# Schematic_Rev2.net
KiCad netlist of a schematic drawn in Altium Designer
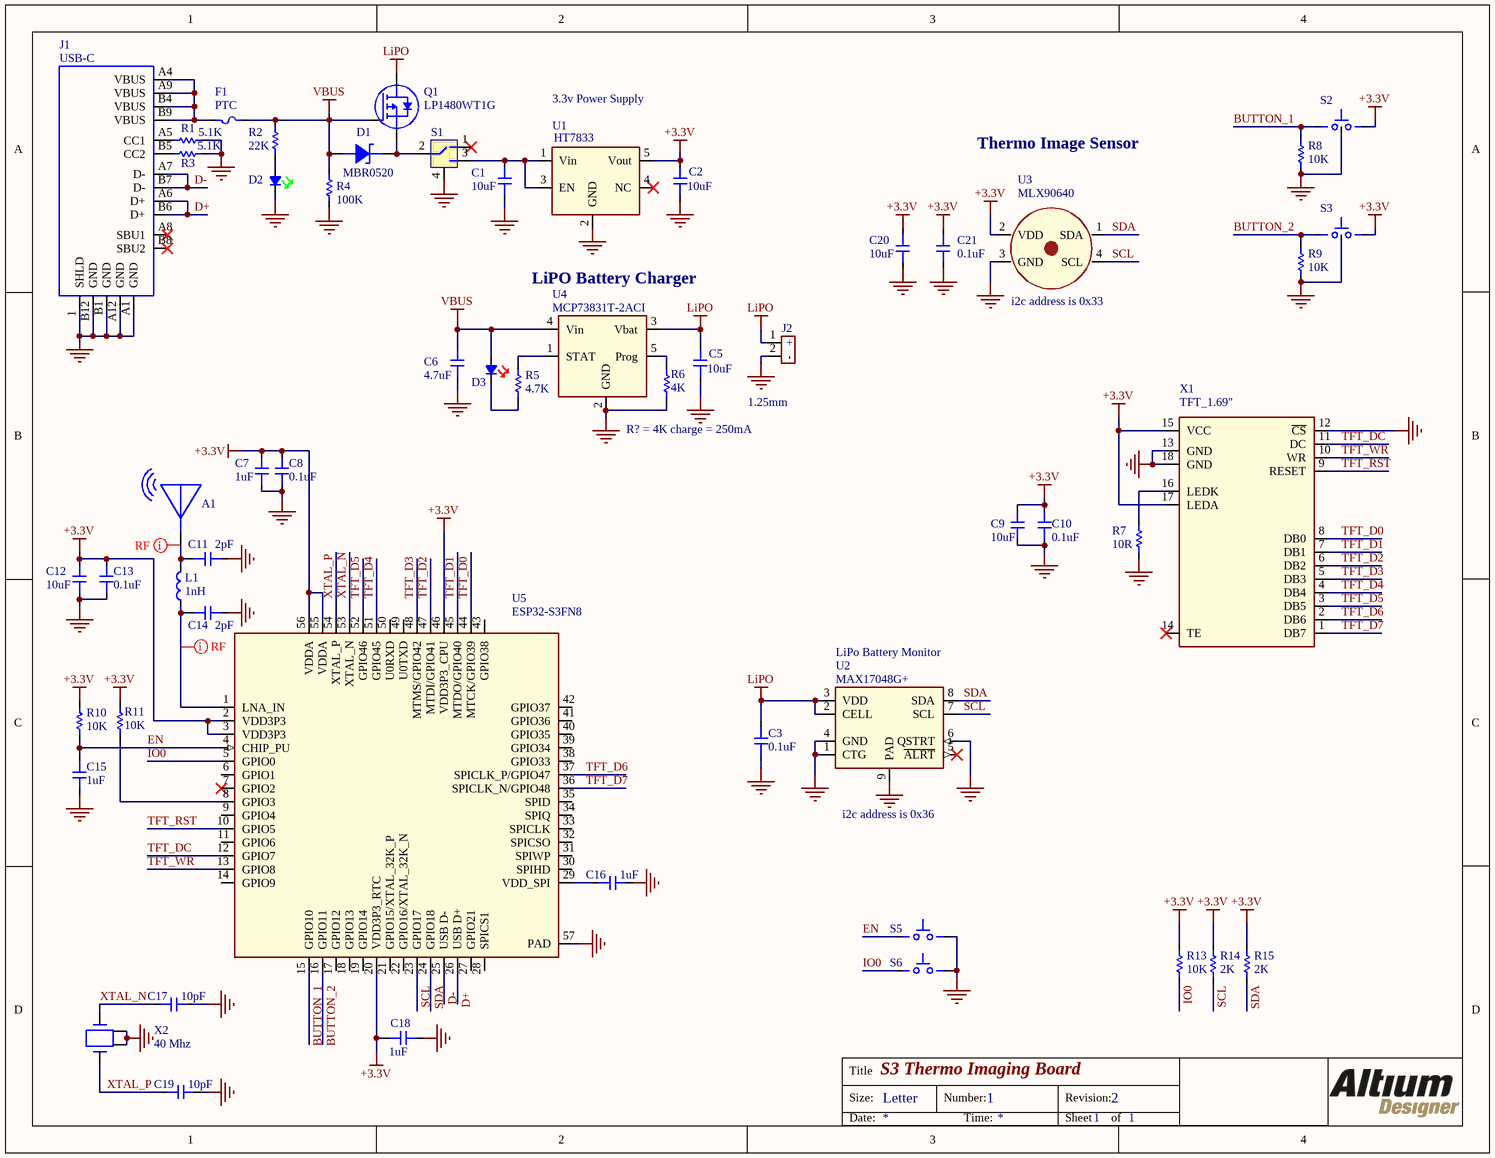
[diagram p0: Schematic_Rev2.SchDoc]

(export (version "E")
  (design (tool "Eeschema 10.0.6"))
  (components
    (comp (ref "A1")
      (value "ANT3216LL00R2400A")
      (footprint "ANT3216LL00R2400A")
      (description "Antenna Chip 2.4Gig")
      (fields (field (name "MANUFACTURER") "YAGEO"))
      (libsource (lib "MAR") (part "ANT3216LL00R2400A"))
    )
    (comp (ref "C1")
      (value "10uF")
      (footprint "CAPC2012X140N")
      (description "CAP 10uF 50V 0805")
      (libsource (lib "MAR") (part "CAP_0805"))
    )
    (comp (ref "C2")
      (value "10uF")
      (footprint "CAPC2012X140N")
      (description "CAP 10uF 50V 0805")
      (libsource (lib "MAR") (part "CAP_0805"))
    )
    (comp (ref "C3")
      (value "0.1uF")
      (footprint "CAPC1005X56N")
      (description "CAP 0.1uF 0402")
      (libsource (lib "MAR") (part "CAP_0402"))
    )
    (comp (ref "C5")
      (value "10uF")
      (footprint "CAPC2012X140N")
      (description "CAP 10uF 50V 0805")
      (libsource (lib "MAR") (part "CAP_0805"))
    )
    (comp (ref "C6")
      (value "4.7uF")
      (footprint "CAPC2012X140N")
      (description "CAP 4.7uF 0805")
      (libsource (lib "MAR") (part "CAP_0805"))
    )
    (comp (ref "C7")
      (value "1uF")
      (footprint "CAPC1608X09L")
      (description "CAP 1uF 0603")
      (libsource (lib "MAR") (part "CAP_0603"))
    )
    (comp (ref "C8")
      (value "0.1uF")
      (footprint "CAPC1608X09L")
      (description "CAP 0.1uF 0603")
      (libsource (lib "MAR") (part "CAP_0603"))
    )
    (comp (ref "C9")
      (value "10uF")
      (footprint "CAPC2012X140N")
      (description "CAP 10uF 0805")
      (libsource (lib "MAR") (part "CAP_0805"))
    )
    (comp (ref "C10")
      (value "0.1uF")
      (footprint "CAPC1608X09L")
      (description "CAP 0.1uF 0603")
      (libsource (lib "MAR") (part "CAP_0603"))
    )
    (comp (ref "C11")
      (value "2pF")
      (footprint "CAPC1005X56N")
      (description "CAP 2pF 0402")
      (libsource (lib "MAR") (part "CAP_0402"))
    )
    (comp (ref "C12")
      (value "10uF")
      (footprint "CAPC2012X140N")
      (description "CAP 10uF 50V 0805")
      (libsource (lib "MAR") (part "CAP_0805"))
    )
    (comp (ref "C13")
      (value "0.1uF")
      (footprint "CAPC1005X56N")
      (description "CAP 0.1uF 0402")
      (libsource (lib "MAR") (part "CAP_0402"))
    )
    (comp (ref "C14")
      (value "2pF")
      (footprint "CAPC1005X56N")
      (description "CAP 2pF 0402")
      (libsource (lib "MAR") (part "CAP_0402"))
    )
    (comp (ref "C15")
      (value "1uF")
      (footprint "CAPC1005X56N")
      (description "CAP 1uF 0402")
      (libsource (lib "MAR") (part "CAP_0402"))
    )
    (comp (ref "C16")
      (value "1uF")
      (footprint "CAPC1005X56N")
      (description "CAP 1uF 0402")
      (libsource (lib "MAR") (part "CAP_0402"))
    )
    (comp (ref "C17")
      (value "10pF")
      (footprint "CAPC1005X56N")
      (description "CAP 10pF 0402")
      (libsource (lib "MAR") (part "CAP_0402"))
    )
    (comp (ref "C18")
      (value "1uF")
      (footprint "CAPC1608X09L")
      (description "CAP 1uF 0603")
      (libsource (lib "MAR") (part "CAP_0603"))
    )
    (comp (ref "C19")
      (value "10pF")
      (footprint "CAPC1005X56N")
      (description "CAP 10pF 0402")
      (libsource (lib "MAR") (part "CAP_0402"))
    )
    (comp (ref "C20")
      (value "10uF")
      (footprint "CAPC2012X140N")
      (description "CAP 10uF 50V 0805")
      (libsource (lib "MAR") (part "CAP_0805"))
    )
    (comp (ref "C21")
      (value "0.1uF")
      (footprint "CAPC1608X09L")
      (description "CAP 0.1uF 0603")
      (libsource (lib "MAR") (part "CAP_0603"))
    )
    (comp (ref "D1")
      (value "MBR0520")
      (footprint "SOD123")
      (description "DIODE SCHOTTKY 20V 500MA SOD-123")
      (fields (field (name "MANUFACTURER") "Micro") (field (name "PART_NUMBER") "C78746"))
      (libsource (lib "MAR") (part "MBR0520-TP"))
    )
    (comp (ref "D2")
      (value "Green Led")
      (footprint "LED1005X40N-Green")
      (description "LED Green 0402")
      (fields (field (name "PART_NUMBER") "C74338"))
      (libsource (lib "MAR") (part "LED_0402_SMALL_GREEN"))
    )
    (comp (ref "D3")
      (value "Red Led")
      (footprint "LED1005X40N-Red")
      (description "LED Red 0402")
      (fields (field (name "PART_NUMBER") "C364556") (field (name "MANUFACTURER") "Lite-On"))
      (libsource (lib "MAR") (part "LED_0402_SMALL_Red"))
    )
    (comp (ref "F1")
      (value "PTC")
      (footprint "RESC1608X06L (0603 FOOTPRINT)")
      (description "PTC FUSE 0.5mA hold, 1A trip 0603")
      (fields (field (name "MANUFACTURER") "JDT Fuse") (field (name "PART_NUMBER") "C2982257"))
      (libsource (lib "MAR") (part "PTC_FUSE_0603"))
    )
    (comp (ref "J1")
      (value "USB-C")
      (footprint "TYPE-C-31-M-12")
      (description "CONN RECPT USB-C")
      (fields (field (name "MANUFACTURER") "KHE") (field (name "PART_NUMBER") "C165948"))
      (libsource (lib "MAR") (part "USB-C"))
    )
    (comp (ref "J2")
      (value "1.5mm")
      (footprint "0530470260")
      (description "MIcro Conn 2POS 1.25mm Pitch Vertical")
      (fields (field (name "PART_NUMBER") "0530470260") (field (name "MANUFACTURER") "Molex"))
      (libsource (lib "MAR") (part "Molex_onn_2Pin_1.25mm_Vert"))
    )
    (comp (ref "L1")
      (value "1nH")
      (footprint "INDC1005X40L")
      (description "Inductor 1nH 0402")
      (libsource (lib "MAR") (part "Inductor"))
    )
    (comp (ref "Q1")
      (value "LP1480WT1G")
      (footprint "SC-70")
      (description "MOSFET P-CH 20V 1.4A SC-70")
      (fields (field (name "MANUFACTURER") "LRC") (field (name "PART_NUMBER") "C172434"))
      (libsource (lib "MAR") (part "LP1480WT1G"))
    )
    (comp (ref "R1")
      (value "5.1K")
      (footprint "RESC1005X40L (0402 FOOTPRINT)")
      (description "RES 5.1K 0402")
      (libsource (lib "MAR") (part "RES_0402"))
    )
    (comp (ref "R2")
      (value "22K")
      (footprint "RESC1005X40L (0402 FOOTPRINT)")
      (description "RES 22K 0402")
      (libsource (lib "MAR") (part "RES_0402"))
    )
    (comp (ref "R3")
      (value "5.1K")
      (footprint "RESC1005X40L (0402 FOOTPRINT)")
      (description "RES 5.1K 0402")
      (libsource (lib "MAR") (part "RES_0402"))
    )
    (comp (ref "R4")
      (value "100K")
      (footprint "RESC1005X40L (0402 FOOTPRINT)")
      (description "RES 100K 0402")
      (libsource (lib "MAR") (part "RES_0402"))
    )
    (comp (ref "R5")
      (value "4.7K")
      (footprint "RESC1005X40L (0402 FOOTPRINT)")
      (description "RES 4.7K 0402")
      (libsource (lib "MAR") (part "RES_0402"))
    )
    (comp (ref "R6")
      (value "4K")
      (footprint "RESC1005X40L (0402 FOOTPRINT)")
      (description "RES 4K 0402")
      (libsource (lib "MAR") (part "RES_0402"))
    )
    (comp (ref "R7")
      (value "10R")
      (footprint "RESC1005X40L (0402 FOOTPRINT)")
      (description "RES 10R 0402")
      (libsource (lib "MAR") (part "RES_0402"))
    )
    (comp (ref "R8")
      (value "10K")
      (footprint "RESC1005X40L (0402 FOOTPRINT)")
      (description "RES 10K 0402")
      (libsource (lib "MAR") (part "RES_0402"))
    )
    (comp (ref "R9")
      (value "10K")
      (footprint "RESC1005X40L (0402 FOOTPRINT)")
      (description "RES 10K 0402")
      (libsource (lib "MAR") (part "RES_0402"))
    )
    (comp (ref "R10")
      (value "10K")
      (footprint "RESC1005X40L (0402 FOOTPRINT)")
      (description "RES 10K 0402")
      (libsource (lib "MAR") (part "RES_0402"))
    )
    (comp (ref "R11")
      (value "10K")
      (footprint "RESC1005X40L (0402 FOOTPRINT)")
      (description "RES 10K 0402")
      (libsource (lib "MAR") (part "RES_0402"))
    )
    (comp (ref "R13")
      (value "10K")
      (footprint "RESC1005X40L (0402 FOOTPRINT)")
      (description "RES 10K 0402")
      (libsource (lib "MAR") (part "RES_0402"))
    )
    (comp (ref "R14")
      (value "2K")
      (footprint "RESC1005X40L (0402 FOOTPRINT)")
      (description "RES 2K 0402")
      (libsource (lib "MAR") (part "RES_0402"))
    )
    (comp (ref "R15")
      (value "2K")
      (footprint "RESC1005X40L (0402 FOOTPRINT)")
      (description "RES 2K 0402")
      (libsource (lib "MAR") (part "RES_0402"))
    )
    (comp (ref "S1")
      (value "SWITCH SLIDE")
      (footprint "K3-1296S-E1")
      (description "SWITCH SLIDE SMD")
      (fields (field (name "MANUFACTURER") "Korean Hroparts Elec") (field (name "PART_NUMBER") "K3-1296S-E1"))
      (libsource (lib "MAR") (part "K3-1296S-E1"))
    )
    (comp (ref "S2")
      (value "Push")
      (footprint "1TS003B-1600-3500A-CT")
      (description "SWITCH TACTILE R/A MICRO")
      (fields (field (name "PART_NUMBER") "C255808") (field (name "MANUFACTURER") "HYP"))
      (libsource (lib "MAR") (part "SWITCH TACTILE R/A_MICRO"))
    )
    (comp (ref "S3")
      (value "Push")
      (footprint "1TS003B-1600-3500A-CT")
      (description "SWITCH TACTILE R/A MICRO")
      (fields (field (name "PART_NUMBER") "C255808") (field (name "MANUFACTURER") "HYP"))
      (libsource (lib "MAR") (part "SWITCH TACTILE R/A_MICRO"))
    )
    (comp (ref "S5")
      (value "~")
      (footprint "TL1015AF160QG")
      (description "SWITCH MOMENTARY")
      (fields (field (name "PART_NUMBER") "TL1015AF160QG"))
      (libsource (lib "MAR") (part "TL1015AF160QG"))
    )
    (comp (ref "S6")
      (value "~")
      (footprint "TL1015AF160QG")
      (description "SWITCH MOMENTARY")
      (fields (field (name "PART_NUMBER") "TL1015AF160QG"))
      (libsource (lib "MAR") (part "TL1015AF160QG"))
    )
    (comp (ref "U1")
      (value "HT7833")
      (footprint "SOT95P280X144-5N")
      (description "IC LDO 3.3V 0.5A SOT23-5")
      (fields (field (name "MANUFACTURER") "Holtek") (field (name "PART_NUMBER") "C164106"))
      (libsource (lib "MAR") (part "HT7833"))
    )
    (comp (ref "U2")
      (value "MAX17048G+")
      (footprint "DFN-8_Smaller")
      (description "IC BATT MON LI-ION 1CELL 8TDFN")
      (fields (field (name "MANUFACTURER") "Analog Devices") (field (name "PART_NUMBER") "MAX17048G+"))
      (libsource (lib "MAR") (part "MAX17048G+"))
    )
    (comp (ref "U3")
      (value "MLX90640")
      (footprint "MLX90640ESF")
      (description "Thermal Image Sensor TO-39")
      (fields (field (name "MANUFACTURER") "Melexis") (field (name "PART_NUMBER") "MLX90640ESF-BAB-000-TU"))
      (libsource (lib "MAR") (part "MLX90640ESF-BAB-000-TU"))
    )
    (comp (ref "U4")
      (value "MCP73831T-2ACI")
      (footprint "SOT95P280X144-5N")
      (description "Charger IC Lithium-Ion/Polymer SOT23-5")
      (fields (field (name "MANUFACTURER") "Microchip") (field (name "PART_NUMBER") "MCP73831T-2ACI/OT"))
      (libsource (lib "MAR") (part "MCP73831T-2ACI/OT"))
    )
    (comp (ref "U5")
      (value "ESP32-S3FN8")
      (footprint "QFN56_0.4mm pitch - Rev2")
      (description "WIFI/Bluetooth, 8M PSRAM, QFN-56 7x7")
      (fields (field (name "MANUFACTURER") "Espressif"))
      (libsource (lib "MAR") (part "ESP32-S3"))
    )
    (comp (ref "X1")
      (value "TFT_1.69\"")
      (footprint "TFT_GLASS 1.69 INCH 8-BIT")
      (description "1.69 INCH TFT 8-BIT PARALLEL BUS")
      (fields (field (name "PART_NUMBER") "ER-TFT1.69-1") (field (name "MANUFACTURER") "BuyDisplay"))
      (libsource (lib "MAR") (part "TFT_GLASS 1.69 INCH COLOR 8-BIT"))
    )
    (comp (ref "X2")
      (value "40 Mhz")
      (footprint "OSC20X16")
      (description "CRYSTAL 40MHZ 10PF SMD")
      (fields (field (name "PART_NUMBER") "ECS-400-10-37B2-CKM") (field (name "MANUFACTURER") "ECS"))
      (libsource (lib "MAR") (part "40Mhz"))
    )
  )
  (nets
    (net (code "1") (name "+3.3V") (class "Default")
      (node (ref "C10") (pin "1") (pintype "passive"))
      (node (ref "C12") (pin "1") (pintype "passive"))
      (node (ref "C13") (pin "1") (pintype "passive"))
      (node (ref "C18") (pin "2") (pintype "passive"))
      (node (ref "C2") (pin "1") (pintype "passive"))
      (node (ref "C20") (pin "1") (pintype "passive"))
      (node (ref "C21") (pin "1") (pintype "passive"))
      (node (ref "C7") (pin "1") (pintype "passive"))
      (node (ref "C8") (pin "1") (pintype "passive"))
      (node (ref "C9") (pin "1") (pintype "passive"))
      (node (ref "R10") (pin "2") (pintype "passive"))
      (node (ref "R11") (pin "1") (pintype "passive"))
      (node (ref "R13") (pin "1") (pintype "passive"))
      (node (ref "R14") (pin "1") (pintype "passive"))
      (node (ref "R15") (pin "1") (pintype "passive"))
      (node (ref "S2") (pin "2") (pinfunction "B_2") (pintype "passive"))
      (node (ref "S3") (pin "2") (pinfunction "B_2") (pintype "passive"))
      (node (ref "U1") (pin "5") (pinfunction "Vout_5") (pintype "passive"))
      (node (ref "U3") (pin "2") (pinfunction "VDD_2") (pintype "power_in"))
      (node (ref "U5") (pin "2") (pinfunction "VDD3P3_2") (pintype "power_in"))
      (node (ref "U5") (pin "20") (pinfunction "VDD3P3_RTC_20") (pintype "power_in"))
      (node (ref "U5") (pin "3") (pinfunction "VDD3P3_3") (pintype "power_in"))
      (node (ref "U5") (pin "46") (pinfunction "VDD3P3_CPU_46") (pintype "power_in"))
      (node (ref "U5") (pin "55") (pinfunction "VDDA_55") (pintype "power_in"))
      (node (ref "U5") (pin "56") (pinfunction "VDDA_56") (pintype "power_in"))
      (node (ref "X1") (pin "15") (pinfunction "VCC_15") (pintype "power_in"))
      (node (ref "X1") (pin "17") (pinfunction "LEDA_17") (pintype "passive"))
    )
    (net (code "2") (name "/BUTTON_1") (class "Default")
      (node (ref "R8") (pin "2") (pintype "passive"))
      (node (ref "S2") (pin "1") (pinfunction "A_1") (pintype "passive"))
      (node (ref "U5") (pin "15") (pinfunction "GPIO10_15") (pintype "passive"))
    )
    (net (code "3") (name "/BUTTON_2") (class "Default")
      (node (ref "R9") (pin "2") (pintype "passive"))
      (node (ref "S3") (pin "1") (pinfunction "A_1") (pintype "passive"))
      (node (ref "U5") (pin "16") (pinfunction "GPIO11_16") (pintype "passive"))
    )
    (net (code "4") (name "/D+") (class "Default")
      (node (ref "J1") (pin "A6") (pinfunction "D+_A6") (pintype "power_in"))
      (node (ref "J1") (pin "B6") (pinfunction "D+_B6") (pintype "power_in"))
      (node (ref "U5") (pin "26") (pinfunction "USB_D+_26") (pintype "passive"))
    )
    (net (code "5") (name "/D-") (class "Default")
      (node (ref "J1") (pin "A7") (pinfunction "D-_A7") (pintype "power_in"))
      (node (ref "J1") (pin "B7") (pinfunction "D-_B7") (pintype "power_in"))
      (node (ref "U5") (pin "25") (pinfunction "USB_D-_25") (pintype "passive"))
    )
    (net (code "6") (name "/EN") (class "Default")
      (node (ref "C15") (pin "1") (pintype "passive"))
      (node (ref "R10") (pin "1") (pintype "passive"))
      (node (ref "S5") (pin "1") (pinfunction "A_1") (pintype "passive"))
      (node (ref "U5") (pin "4") (pinfunction "CHIP_PU_4") (pintype "input"))
    )
    (net (code "7") (name "/IO0") (class "Default")
      (node (ref "R13") (pin "2") (pintype "passive"))
      (node (ref "S6") (pin "1") (pinfunction "A_1") (pintype "passive"))
      (node (ref "U5") (pin "5") (pinfunction "GPIO0_5") (pintype "passive"))
    )
    (net (code "8") (name "/SCL") (class "Default")
      (node (ref "R14") (pin "2") (pintype "passive"))
      (node (ref "U2") (pin "7") (pinfunction "SCL_7") (pintype "passive"))
      (node (ref "U3") (pin "4") (pinfunction "SCL_4") (pintype "passive"))
      (node (ref "U5") (pin "23") (pinfunction "GPIO17_23") (pintype "passive"))
    )
    (net (code "9") (name "/SDA") (class "Default")
      (node (ref "R15") (pin "2") (pintype "passive"))
      (node (ref "U2") (pin "8") (pinfunction "SDA_8") (pintype "passive"))
      (node (ref "U3") (pin "1") (pinfunction "SDA_1") (pintype "passive"))
      (node (ref "U5") (pin "24") (pinfunction "GPIO18_24") (pintype "passive"))
    )
    (net (code "10") (name "/TFT_D0") (class "Default")
      (node (ref "U5") (pin "44") (pinfunction "MTCK/GPIO39_44") (pintype "passive"))
      (node (ref "X1") (pin "8") (pinfunction "DB0_8") (pintype "passive"))
    )
    (net (code "11") (name "/TFT_D1") (class "Default")
      (node (ref "U5") (pin "45") (pinfunction "MTDO/GPIO40_45") (pintype "passive"))
      (node (ref "X1") (pin "7") (pinfunction "DB1_7") (pintype "passive"))
    )
    (net (code "12") (name "/TFT_D2") (class "Default")
      (node (ref "U5") (pin "47") (pinfunction "MTDI/GPIO41_47") (pintype "passive"))
      (node (ref "X1") (pin "6") (pinfunction "DB2_6") (pintype "passive"))
    )
    (net (code "13") (name "/TFT_D3") (class "Default")
      (node (ref "U5") (pin "48") (pinfunction "MTMS/GPIO42_48") (pintype "passive"))
      (node (ref "X1") (pin "5") (pinfunction "DB3_5") (pintype "passive"))
    )
    (net (code "14") (name "/TFT_D4") (class "Default")
      (node (ref "U5") (pin "51") (pinfunction "GPIO45_51") (pintype "passive"))
      (node (ref "X1") (pin "4") (pinfunction "DB4_4") (pintype "passive"))
    )
    (net (code "15") (name "/TFT_D5") (class "Default")
      (node (ref "U5") (pin "52") (pinfunction "GPIO46_52") (pintype "passive"))
      (node (ref "X1") (pin "3") (pinfunction "DB5_3") (pintype "passive"))
    )
    (net (code "16") (name "/TFT_D6") (class "Default")
      (node (ref "U5") (pin "37") (pinfunction "SPICLK_P/GPIO47_37") (pintype "passive"))
      (node (ref "X1") (pin "2") (pinfunction "DB6_2") (pintype "passive"))
    )
    (net (code "17") (name "/TFT_D7") (class "Default")
      (node (ref "U5") (pin "36") (pinfunction "SPICLK_N/GPIO48_36") (pintype "passive"))
      (node (ref "X1") (pin "1") (pinfunction "DB7_1") (pintype "passive"))
    )
    (net (code "18") (name "/TFT_DC") (class "Default")
      (node (ref "U5") (pin "12") (pinfunction "GPIO7_12") (pintype "passive"))
      (node (ref "X1") (pin "11") (pinfunction "DC_11") (pintype "passive"))
    )
    (net (code "19") (name "/TFT_RST") (class "Default")
      (node (ref "U5") (pin "10") (pinfunction "GPIO5_10") (pintype "passive"))
      (node (ref "X1") (pin "9") (pinfunction "RESET_9") (pintype "passive"))
    )
    (net (code "20") (name "/TFT_WR") (class "Default")
      (node (ref "U5") (pin "13") (pinfunction "GPIO8_13") (pintype "passive"))
      (node (ref "X1") (pin "10") (pinfunction "WR_10") (pintype "passive"))
    )
    (net (code "21") (name "/XTAL_N") (class "Default")
      (node (ref "C17") (pin "1") (pintype "passive"))
      (node (ref "U5") (pin "53") (pinfunction "XTAL_N_53") (pintype "passive"))
      (node (ref "X2") (pin "3") (pinfunction "3_3") (pintype "passive"))
    )
    (net (code "22") (name "/XTAL_P") (class "Default")
      (node (ref "C19") (pin "1") (pintype "passive"))
      (node (ref "U5") (pin "54") (pinfunction "XTAL_P_54") (pintype "passive"))
      (node (ref "X2") (pin "1") (pinfunction "1_1") (pintype "passive"))
    )
    (net (code "23") (name "GND") (class "Default")
      (node (ref "C1") (pin "2") (pintype "passive"))
      (node (ref "C10") (pin "2") (pintype "passive"))
      (node (ref "C11") (pin "2") (pintype "passive"))
      (node (ref "C12") (pin "2") (pintype "passive"))
      (node (ref "C13") (pin "2") (pintype "passive"))
      (node (ref "C14") (pin "2") (pintype "passive"))
      (node (ref "C15") (pin "2") (pintype "passive"))
      (node (ref "C16") (pin "2") (pintype "passive"))
      (node (ref "C17") (pin "2") (pintype "passive"))
      (node (ref "C18") (pin "1") (pintype "passive"))
      (node (ref "C19") (pin "2") (pintype "passive"))
      (node (ref "C2") (pin "2") (pintype "passive"))
      (node (ref "C20") (pin "2") (pintype "passive"))
      (node (ref "C21") (pin "2") (pintype "passive"))
      (node (ref "C3") (pin "2") (pintype "passive"))
      (node (ref "C5") (pin "2") (pintype "passive"))
      (node (ref "C6") (pin "2") (pintype "passive"))
      (node (ref "C7") (pin "2") (pintype "passive"))
      (node (ref "C8") (pin "2") (pintype "passive"))
      (node (ref "C9") (pin "2") (pintype "passive"))
      (node (ref "D2") (pin "1") (pintype "passive"))
      (node (ref "J1") (pin "1") (pinfunction "SHLD_1") (pintype "power_in"))
      (node (ref "J1") (pin "A1") (pinfunction "GND_A1") (pintype "power_in"))
      (node (ref "J1") (pin "A12") (pinfunction "GND_A12") (pintype "power_in"))
      (node (ref "J1") (pin "B1") (pinfunction "GND_B1") (pintype "power_in"))
      (node (ref "J1") (pin "B12") (pinfunction "GND_B12") (pintype "passive"))
      (node (ref "J2") (pin "2") (pintype "passive"))
      (node (ref "R1") (pin "1") (pintype "passive"))
      (node (ref "R3") (pin "1") (pintype "passive"))
      (node (ref "R4") (pin "2") (pintype "passive"))
      (node (ref "R6") (pin "1") (pintype "passive"))
      (node (ref "R7") (pin "2") (pintype "passive"))
      (node (ref "R8") (pin "1") (pintype "passive"))
      (node (ref "R9") (pin "1") (pintype "passive"))
      (node (ref "S1") (pin "4") (pinfunction "4_4") (pintype "passive"))
      (node (ref "S2") (pin "3") (pinfunction "3_3") (pintype "passive"))
      (node (ref "S3") (pin "3") (pinfunction "3_3") (pintype "passive"))
      (node (ref "S5") (pin "2") (pinfunction "B_2") (pintype "passive"))
      (node (ref "S6") (pin "2") (pinfunction "B_2") (pintype "passive"))
      (node (ref "U1") (pin "2") (pinfunction "GND_2") (pintype "power_in"))
      (node (ref "U2") (pin "1") (pinfunction "CTG_1") (pintype "power_in"))
      (node (ref "U2") (pin "4") (pinfunction "GND_4") (pintype "power_in"))
      (node (ref "U2") (pin "6") (pinfunction "QSTRT_6") (pintype "input"))
      (node (ref "U2") (pin "9") (pinfunction "PAD_9") (pintype "power_in"))
      (node (ref "U3") (pin "3") (pinfunction "GND_3") (pintype "power_in"))
      (node (ref "U4") (pin "2") (pinfunction "GND_2") (pintype "power_in"))
      (node (ref "U5") (pin "57") (pinfunction "PAD_57") (pintype "power_in"))
      (node (ref "X1") (pin "12") (pinfunction "~{CS}_12") (pintype "passive"))
      (node (ref "X1") (pin "13") (pinfunction "GND_13") (pintype "power_in"))
      (node (ref "X1") (pin "18") (pinfunction "GND_18") (pintype "power_in"))
      (node (ref "X2") (pin "2") (pinfunction "2_2") (pintype "power_in"))
      (node (ref "X2") (pin "4") (pinfunction "4_4") (pintype "power_in"))
    )
    (net (code "24") (name "LiPO") (class "Default")
      (node (ref "C3") (pin "1") (pintype "passive"))
      (node (ref "C5") (pin "1") (pintype "passive"))
      (node (ref "J2") (pin "1") (pintype "passive"))
      (node (ref "Q1") (pin "3") (pinfunction "D_3") (pintype "passive"))
      (node (ref "U2") (pin "2") (pinfunction "CELL_2") (pintype "power_in"))
      (node (ref "U2") (pin "3") (pinfunction "VDD_3") (pintype "power_in"))
      (node (ref "U4") (pin "3") (pinfunction "Vbat_3") (pintype "passive"))
    )
    (net (code "25") (name "Net-(A1-Pad1)") (class "Default")
      (node (ref "A1") (pin "1") (pintype "passive"))
      (node (ref "C11") (pin "1") (pintype "passive"))
      (node (ref "L1") (pin "1") (pinfunction "1_1") (pintype "passive"))
    )
    (net (code "26") (name "Net-(D1-Cathode)") (class "Default")
      (node (ref "D1") (pin "1") (pinfunction "Cathode_1") (pintype "passive"))
      (node (ref "Q1") (pin "2") (pinfunction "S_2") (pintype "passive"))
      (node (ref "S1") (pin "2") (pinfunction "2_2") (pintype "passive"))
    )
    (net (code "27") (name "Net-(D2-Pad2)") (class "Default")
      (node (ref "D2") (pin "2") (pintype "passive"))
      (node (ref "R2") (pin "1") (pintype "passive"))
    )
    (net (code "28") (name "Net-(D3-Pad1)") (class "Default")
      (node (ref "D3") (pin "1") (pintype "passive"))
      (node (ref "R5") (pin "1") (pintype "passive"))
    )
    (net (code "29") (name "Net-(F1-Pad2)") (class "Default")
      (node (ref "F1") (pin "2") (pintype "passive"))
      (node (ref "J1") (pin "A4") (pinfunction "VBUS_A4") (pintype "passive"))
      (node (ref "J1") (pin "A9") (pinfunction "VBUS_A9") (pintype "power_in"))
      (node (ref "J1") (pin "B4") (pinfunction "VBUS_B4") (pintype "power_in"))
      (node (ref "J1") (pin "B9") (pinfunction "VBUS_B9") (pintype "passive"))
    )
    (net (code "30") (name "Net-(J1-CC1)") (class "Default")
      (node (ref "J1") (pin "A5") (pinfunction "CC1_A5") (pintype "power_in"))
      (node (ref "R1") (pin "2") (pintype "passive"))
    )
    (net (code "31") (name "Net-(J1-CC2)") (class "Default")
      (node (ref "J1") (pin "B5") (pinfunction "CC2_B5") (pintype "power_in"))
      (node (ref "R3") (pin "2") (pintype "passive"))
    )
    (net (code "32") (name "Net-(U1-EN)") (class "Default")
      (node (ref "C1") (pin "1") (pintype "passive"))
      (node (ref "S1") (pin "3") (pinfunction "3_3") (pintype "passive"))
      (node (ref "U1") (pin "1") (pinfunction "Vin_1") (pintype "passive"))
      (node (ref "U1") (pin "3") (pinfunction "EN_3") (pintype "passive"))
    )
    (net (code "33") (name "Net-(U4-Prog)") (class "Default")
      (node (ref "R6") (pin "2") (pintype "passive"))
      (node (ref "U4") (pin "5") (pinfunction "Prog_5") (pintype "passive"))
    )
    (net (code "34") (name "Net-(U4-STAT)") (class "Default")
      (node (ref "R5") (pin "2") (pintype "passive"))
      (node (ref "U4") (pin "1") (pinfunction "STAT_1") (pintype "passive"))
    )
    (net (code "35") (name "Net-(U5-GPIO3)") (class "Default")
      (node (ref "R11") (pin "2") (pintype "passive"))
      (node (ref "U5") (pin "8") (pinfunction "GPIO3_8") (pintype "passive"))
    )
    (net (code "36") (name "Net-(U5-LNA_IN)") (class "Default")
      (node (ref "C14") (pin "1") (pintype "passive"))
      (node (ref "L1") (pin "2") (pinfunction "2_2") (pintype "passive"))
      (node (ref "U5") (pin "1") (pinfunction "LNA_IN_1") (pintype "passive"))
    )
    (net (code "37") (name "Net-(U5-VDD_SPI)") (class "Default")
      (node (ref "C16") (pin "1") (pintype "passive"))
      (node (ref "U5") (pin "29") (pinfunction "VDD_SPI_29") (pintype "power_in"))
    )
    (net (code "38") (name "Net-(X1-LEDK)") (class "Default")
      (node (ref "R7") (pin "1") (pintype "passive"))
      (node (ref "X1") (pin "16") (pinfunction "LEDK_16") (pintype "passive"))
    )
    (net (code "39") (name "VBUS") (class "Default")
      (node (ref "C6") (pin "1") (pintype "passive"))
      (node (ref "D1") (pin "2") (pinfunction "Annode_2") (pintype "passive"))
      (node (ref "D3") (pin "2") (pintype "passive"))
      (node (ref "F1") (pin "1") (pintype "passive"))
      (node (ref "Q1") (pin "1") (pinfunction "G_1") (pintype "passive"))
      (node (ref "R2") (pin "2") (pintype "passive"))
      (node (ref "R4") (pin "1") (pintype "passive"))
      (node (ref "U4") (pin "4") (pinfunction "Vin_4") (pintype "passive"))
    )
    (net (code "40") (name "unconnected-(J1-SBU1-PadA8)") (class "Default")
      (node (ref "J1") (pin "A8") (pinfunction "SBU1_A8") (pintype "power_in+no_connect"))
    )
    (net (code "41") (name "unconnected-(J1-SBU2-PadB8)") (class "Default")
      (node (ref "J1") (pin "B8") (pinfunction "SBU2_B8") (pintype "power_in+no_connect"))
    )
    (net (code "42") (name "unconnected-(S1-Pad1)") (class "Default")
      (node (ref "S1") (pin "1") (pinfunction "1_1") (pintype "passive+no_connect"))
    )
    (net (code "43") (name "unconnected-(U1-NC-Pad4)") (class "Default")
      (node (ref "U1") (pin "4") (pinfunction "NC_4") (pintype "passive+no_connect"))
    )
    (net (code "44") (name "unconnected-(U2-~{ALRT}-Pad5)") (class "Default")
      (node (ref "U2") (pin "5") (pinfunction "~{ALRT}_5") (pintype "output+no_connect"))
    )
    (net (code "45") (name "unconnected-(U5-GPIO1-Pad6)") (class "Default")
      (node (ref "U5") (pin "6") (pinfunction "GPIO1_6") (pintype "passive"))
    )
    (net (code "46") (name "unconnected-(U5-GPIO2-Pad7)") (class "Default")
      (node (ref "U5") (pin "7") (pinfunction "GPIO2_7") (pintype "passive+no_connect"))
    )
    (net (code "47") (name "unconnected-(U5-GPIO4-Pad9)") (class "Default")
      (node (ref "U5") (pin "9") (pinfunction "GPIO4_9") (pintype "passive"))
    )
    (net (code "48") (name "unconnected-(U5-GPIO6-Pad11)") (class "Default")
      (node (ref "U5") (pin "11") (pinfunction "GPIO6_11") (pintype "passive"))
    )
    (net (code "49") (name "unconnected-(U5-GPIO9-Pad14)") (class "Default")
      (node (ref "U5") (pin "14") (pinfunction "GPIO9_14") (pintype "passive"))
    )
    (net (code "50") (name "unconnected-(U5-GPIO12-Pad17)") (class "Default")
      (node (ref "U5") (pin "17") (pinfunction "GPIO12_17") (pintype "passive"))
    )
    (net (code "51") (name "unconnected-(U5-GPIO13-Pad18)") (class "Default")
      (node (ref "U5") (pin "18") (pinfunction "GPIO13_18") (pintype "passive"))
    )
    (net (code "52") (name "unconnected-(U5-GPIO14-Pad19)") (class "Default")
      (node (ref "U5") (pin "19") (pinfunction "GPIO14_19") (pintype "passive"))
    )
    (net (code "53") (name "unconnected-(U5-GPIO15{slash}XTAL_32K_P-Pad21)") (class "Default")
      (node (ref "U5") (pin "21") (pinfunction "GPIO15/XTAL_32K_P_21") (pintype "passive"))
    )
    (net (code "54") (name "unconnected-(U5-GPIO16{slash}XTAL_32K_N-Pad22)") (class "Default")
      (node (ref "U5") (pin "22") (pinfunction "GPIO16/XTAL_32K_N_22") (pintype "passive"))
    )
    (net (code "55") (name "unconnected-(U5-GPIO21-Pad27)") (class "Default")
      (node (ref "U5") (pin "27") (pinfunction "GPIO21_27") (pintype "passive"))
    )
    (net (code "56") (name "unconnected-(U5-GPIO33-Pad38)") (class "Default")
      (node (ref "U5") (pin "38") (pinfunction "GPIO33_38") (pintype "passive"))
    )
    (net (code "57") (name "unconnected-(U5-GPIO34-Pad39)") (class "Default")
      (node (ref "U5") (pin "39") (pinfunction "GPIO34_39") (pintype "passive"))
    )
    (net (code "58") (name "unconnected-(U5-GPIO35-Pad40)") (class "Default")
      (node (ref "U5") (pin "40") (pinfunction "GPIO35_40") (pintype "passive"))
    )
    (net (code "59") (name "unconnected-(U5-GPIO36-Pad41)") (class "Default")
      (node (ref "U5") (pin "41") (pinfunction "GPIO36_41") (pintype "passive"))
    )
    (net (code "60") (name "unconnected-(U5-GPIO37-Pad42)") (class "Default")
      (node (ref "U5") (pin "42") (pinfunction "GPIO37_42") (pintype "passive"))
    )
    (net (code "61") (name "unconnected-(U5-GPIO38-Pad43)") (class "Default")
      (node (ref "U5") (pin "43") (pinfunction "GPIO38_43") (pintype "passive"))
    )
    (net (code "62") (name "unconnected-(U5-SPICLK-Pad33)") (class "Default")
      (node (ref "U5") (pin "33") (pinfunction "SPICLK_33") (pintype "passive"))
    )
    (net (code "63") (name "unconnected-(U5-SPICS1-Pad28)") (class "Default")
      (node (ref "U5") (pin "28") (pinfunction "SPICS1_28") (pintype "passive"))
    )
    (net (code "64") (name "unconnected-(U5-SPICSO-Pad32)") (class "Default")
      (node (ref "U5") (pin "32") (pinfunction "SPICSO_32") (pintype "passive"))
    )
    (net (code "65") (name "unconnected-(U5-SPID-Pad35)") (class "Default")
      (node (ref "U5") (pin "35") (pinfunction "SPID_35") (pintype "passive"))
    )
    (net (code "66") (name "unconnected-(U5-SPIHD-Pad30)") (class "Default")
      (node (ref "U5") (pin "30") (pinfunction "SPIHD_30") (pintype "passive"))
    )
    (net (code "67") (name "unconnected-(U5-SPIQ-Pad34)") (class "Default")
      (node (ref "U5") (pin "34") (pinfunction "SPIQ_34") (pintype "passive"))
    )
    (net (code "68") (name "unconnected-(U5-SPIWP-Pad31)") (class "Default")
      (node (ref "U5") (pin "31") (pinfunction "SPIWP_31") (pintype "passive"))
    )
    (net (code "69") (name "unconnected-(U5-U0RXD-Pad50)") (class "Default")
      (node (ref "U5") (pin "50") (pinfunction "U0RXD_50") (pintype "passive"))
    )
    (net (code "70") (name "unconnected-(U5-U0TXD-Pad49)") (class "Default")
      (node (ref "U5") (pin "49") (pinfunction "U0TXD_49") (pintype "passive"))
    )
    (net (code "71") (name "unconnected-(X1-TE-Pad14)") (class "Default")
      (node (ref "X1") (pin "14") (pinfunction "TE_14") (pintype "passive+no_connect"))
    )
  )
)
